# Encoder_-_32_bit.net
KiCad netlist of a schematic drawn in Altium Designer
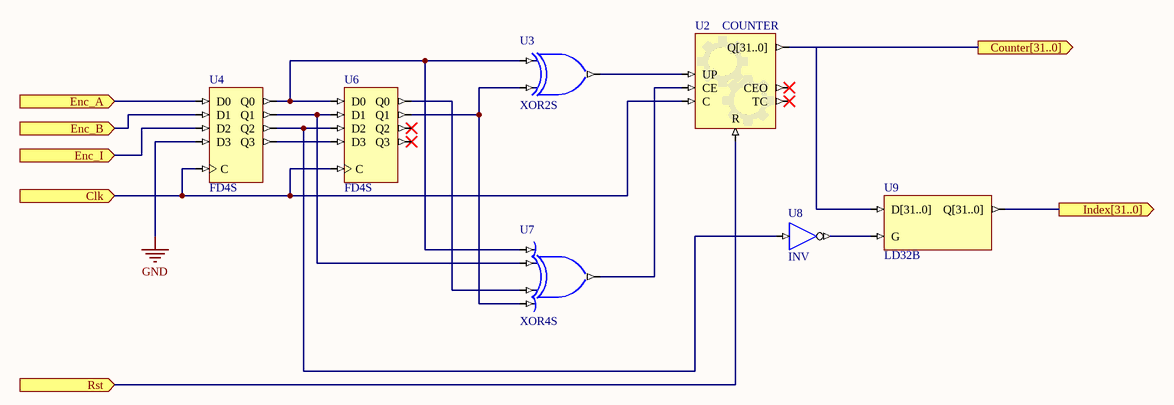
[diagram p0: Encoder - 32 bit.SchDoc]

(export (version "E")
  (design (tool "Eeschema 10.0.6"))
  (components
    (comp (ref "U2")
      (value "COUNTER")
      (description "Configurable Counter")
      (fields (field (name "PUBLISHER") "Altium Limited"))
      (libsource (lib "FPGA Configurable Generic") (part "COUNTER"))
    )
    (comp (ref "U3")
      (value "XOR2S")
      (description "2-Input Exclusive-OR Gate, Single Pin Version")
      (fields (field (name "PUBLISHER") "Altium Limited"))
      (libsource (lib "FPGA Generic") (part "XOR2S"))
    )
    (comp (ref "U4")
      (value "FD4S")
      (description "4-Bit D-Type Flip-Flop, Single Pin Version")
      (fields (field (name "PUBLISHER") "Altium Limited"))
      (libsource (lib "FPGA Generic") (part "FD4S"))
    )
    (comp (ref "U6")
      (value "FD4S")
      (description "4-Bit D-Type Flip-Flop, Single Pin Version")
      (fields (field (name "PUBLISHER") "Altium Limited"))
      (libsource (lib "FPGA Generic") (part "FD4S"))
    )
    (comp (ref "U7")
      (value "XOR4S")
      (description "4-Input Exclusive-OR Gate, Single Pin Version")
      (fields (field (name "PUBLISHER") "Altium Limited"))
      (libsource (lib "FPGA Generic") (part "XOR4S"))
    )
    (comp (ref "U8")
      (value "INV")
      (description "Inverter")
      (fields (field (name "PUBLISHER") "Altium Limited"))
      (libsource (lib "FPGA Generic") (part "INV"))
    )
    (comp (ref "U9")
      (value "LD32B")
      (description "32-Bit Transparent Data Latch, Bus Version")
      (fields (field (name "PUBLISHER") "Altium Limited"))
      (libsource (lib "FPGA Generic") (part "LD32B"))
    )
  )
  (nets
    (net (code "65") (name "/Clk") (class "Default")
      (node (ref "U2") (pin "C") (pinfunction "C_C") (pintype "input"))
      (node (ref "U4") (pin "C") (pinfunction "C_C") (pintype "input"))
      (node (ref "U6") (pin "C") (pinfunction "C_C") (pintype "input"))
    )
    (net (code "66") (name "/Counter[31..0]") (class "Default")
      (node (ref "U2") (pin "Q[31..0]") (pinfunction "Q[31..0]_Q[31..0]") (pintype "output"))
    )
    (net (code "67") (name "/Enc_A") (class "Default")
      (node (ref "U4") (pin "D0") (pinfunction "D0_D0") (pintype "input"))
    )
    (net (code "68") (name "/Enc_B") (class "Default")
      (node (ref "U4") (pin "D1") (pinfunction "D1_D1") (pintype "input"))
    )
    (net (code "69") (name "/Enc_I") (class "Default")
      (node (ref "U4") (pin "D2") (pinfunction "D2_D2") (pintype "input"))
    )
    (net (code "70") (name "/Index[31..0]") (class "Default")
      (node (ref "U9") (pin "Q[31..0]") (pinfunction "Q[31..0]_Q[31..0]") (pintype "output"))
    )
    (net (code "71") (name "/Rst") (class "Default")
      (node (ref "U2") (pin "R") (pinfunction "R_R") (pintype "input"))
    )
    (net (code "72") (name "GND") (class "Default")
      (node (ref "U4") (pin "D3") (pinfunction "D3_D3") (pintype "input"))
    )
    (net (code "73") (name "Net-(U2-PadCE)") (class "Default")
      (node (ref "U2") (pin "CE") (pinfunction "CE_CE") (pintype "input"))
      (node (ref "U7") (pin "O") (pinfunction "O_O") (pintype "output"))
    )
    (net (code "74") (name "Net-(U2-PadUP)") (class "Default")
      (node (ref "U2") (pin "UP") (pinfunction "UP_UP") (pintype "input"))
      (node (ref "U3") (pin "O") (pinfunction "O_O") (pintype "output"))
    )
    (net (code "75") (name "Net-(U3-PadI0)") (class "Default")
      (node (ref "U3") (pin "I0") (pinfunction "I0_I0") (pintype "input"))
      (node (ref "U4") (pin "Q0") (pinfunction "Q0_Q0") (pintype "output"))
      (node (ref "U6") (pin "D0") (pinfunction "D0_D0") (pintype "input"))
      (node (ref "U7") (pin "I0") (pinfunction "I0_I0") (pintype "input"))
    )
    (net (code "76") (name "Net-(U3-PadI1)") (class "Default")
      (node (ref "U3") (pin "I1") (pinfunction "I1_I1") (pintype "input"))
      (node (ref "U6") (pin "Q1") (pinfunction "Q1_Q1") (pintype "output"))
      (node (ref "U7") (pin "I3") (pinfunction "I3_I3") (pintype "input"))
    )
    (net (code "77") (name "Net-(U4-PadQ1)") (class "Default")
      (node (ref "U4") (pin "Q1") (pinfunction "Q1_Q1") (pintype "output"))
      (node (ref "U6") (pin "D1") (pinfunction "D1_D1") (pintype "input"))
      (node (ref "U7") (pin "I1") (pinfunction "I1_I1") (pintype "input"))
    )
    (net (code "78") (name "Net-(U4-PadQ2)") (class "Default")
      (node (ref "U4") (pin "Q2") (pinfunction "Q2_Q2") (pintype "output"))
      (node (ref "U6") (pin "D2") (pinfunction "D2_D2") (pintype "input"))
      (node (ref "U8") (pin "I") (pinfunction "I_I") (pintype "input"))
    )
    (net (code "79") (name "Net-(U4-PadQ3)") (class "Default")
      (node (ref "U4") (pin "Q3") (pinfunction "Q3_Q3") (pintype "output"))
      (node (ref "U6") (pin "D3") (pinfunction "D3_D3") (pintype "input"))
    )
    (net (code "80") (name "Net-(U6-PadQ0)") (class "Default")
      (node (ref "U6") (pin "Q0") (pinfunction "Q0_Q0") (pintype "output"))
      (node (ref "U7") (pin "I2") (pinfunction "I2_I2") (pintype "input"))
    )
    (net (code "81") (name "Net-(U8-PadO)") (class "Default")
      (node (ref "U8") (pin "O") (pinfunction "O_O") (pintype "output"))
      (node (ref "U9") (pin "G") (pinfunction "G_G") (pintype "input"))
    )
    (net (code "82") (name "unconnected-(U2-PadCEO)") (class "Default")
      (node (ref "U2") (pin "CEO") (pinfunction "CEO_CEO") (pintype "output+no_connect"))
    )
    (net (code "83") (name "unconnected-(U2-PadTC)") (class "Default")
      (node (ref "U2") (pin "TC") (pinfunction "TC_TC") (pintype "output+no_connect"))
    )
    (net (code "84") (name "unconnected-(U6-PadQ2)") (class "Default")
      (node (ref "U6") (pin "Q2") (pinfunction "Q2_Q2") (pintype "output+no_connect"))
    )
    (net (code "85") (name "unconnected-(U6-PadQ3)") (class "Default")
      (node (ref "U6") (pin "Q3") (pinfunction "Q3_Q3") (pintype "output+no_connect"))
    )
    (net (code "86") (name "unconnected-(U9-PadD[31..0])") (class "Default")
      (node (ref "U9") (pin "D[31..0]") (pinfunction "D[31..0]_D[31..0]") (pintype "input"))
    )
  )
)
